# xyControl.net
KiCad netlist of a schematic drawn in EAGLE
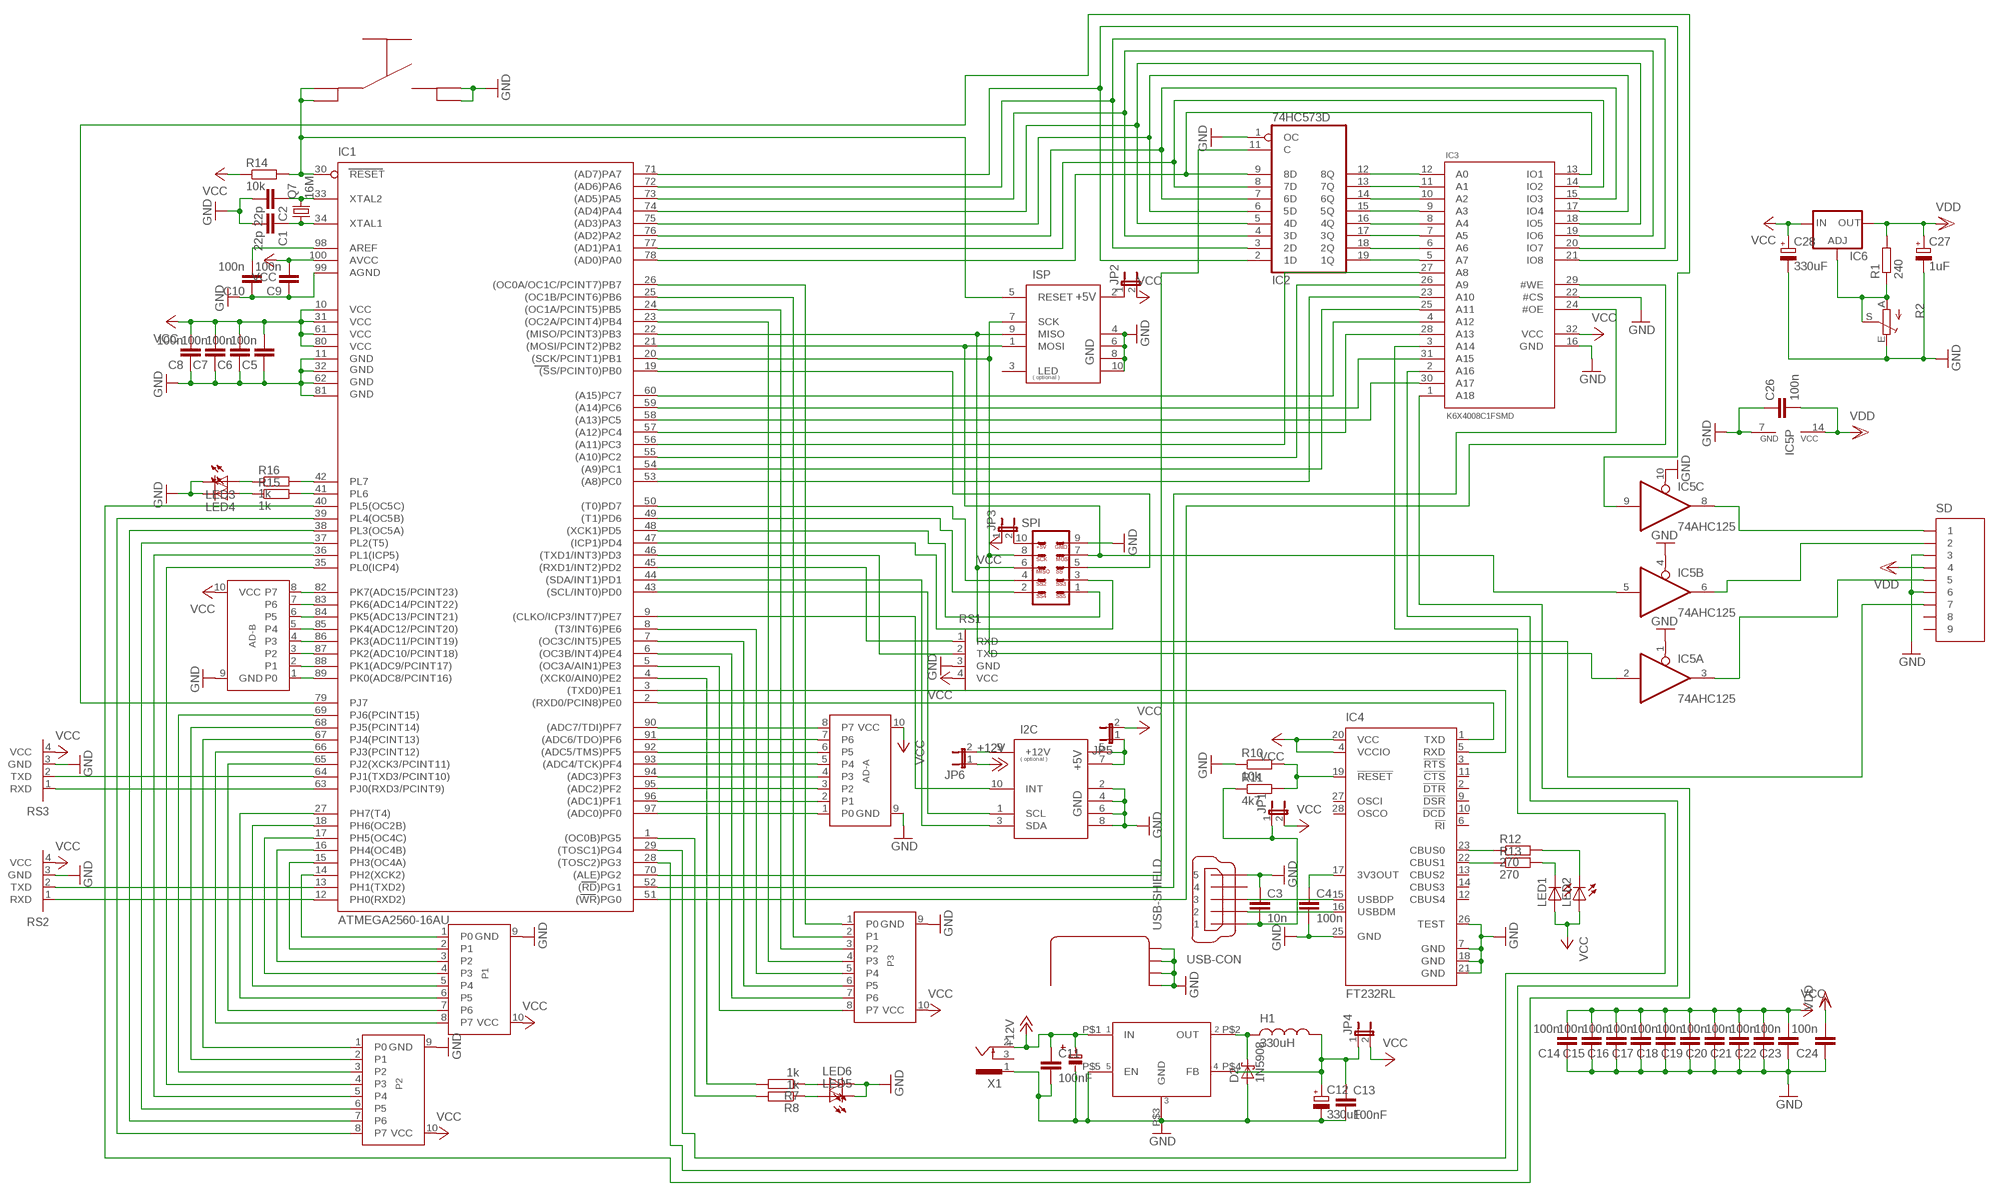
[diagram p0: schematic, sheet 1]

(export (version "E")
  (design (tool "Eeschema 10.0.6"))
  (components
    (comp (ref "AD-A")
      (value "PORT")
      (footprint "eagle-import:ML10")
      (libsource (lib "eagle-import") (part "PORT"))
    )
    (comp (ref "AD-B")
      (value "PORT")
      (footprint "eagle-import:ML10")
      (libsource (lib "eagle-import") (part "PORT"))
    )
    (comp (ref "C1")
      (value "22p")
      (footprint "eagle-import:C0603K")
      (libsource (lib "eagle-import") (part "C-EUC0603K"))
    )
    (comp (ref "C2")
      (value "22p")
      (footprint "eagle-import:C0603K")
      (libsource (lib "eagle-import") (part "C-EUC0603K"))
    )
    (comp (ref "C3")
      (value "10n")
      (footprint "eagle-import:C0603K")
      (libsource (lib "eagle-import") (part "C-EUC0603K"))
    )
    (comp (ref "C4")
      (value "100n")
      (footprint "eagle-import:C0603K")
      (libsource (lib "eagle-import") (part "C-EUC0603K"))
    )
    (comp (ref "C5")
      (value "100n")
      (footprint "eagle-import:C0603K")
      (libsource (lib "eagle-import") (part "C-EUC0603K"))
    )
    (comp (ref "C6")
      (value "100n")
      (footprint "eagle-import:C0603K")
      (libsource (lib "eagle-import") (part "C-EUC0603K"))
    )
    (comp (ref "C7")
      (value "100n")
      (footprint "eagle-import:C0603K")
      (libsource (lib "eagle-import") (part "C-EUC0603K"))
    )
    (comp (ref "C8")
      (value "100n")
      (footprint "eagle-import:C0603K")
      (libsource (lib "eagle-import") (part "C-EUC0603K"))
    )
    (comp (ref "C9")
      (value "100n")
      (footprint "eagle-import:C0603K")
      (libsource (lib "eagle-import") (part "C-EUC0603K"))
    )
    (comp (ref "C10")
      (value "100n")
      (footprint "eagle-import:C0603K")
      (libsource (lib "eagle-import") (part "C-EUC0603K"))
    )
    (comp (ref "C11")
      (value "100nF")
      (footprint "eagle-import:C0603K")
      (libsource (lib "eagle-import") (part "C-EUC0603K"))
    )
    (comp (ref "C12")
      (value "330uF")
      (footprint "eagle-import:PANASONIC_F")
      (libsource (lib "eagle-import") (part "CPOL-EUF"))
    )
    (comp (ref "C13")
      (value "100nF")
      (footprint "eagle-import:C0603K")
      (libsource (lib "eagle-import") (part "C-EUC0603K"))
    )
    (comp (ref "C14")
      (value "100n")
      (footprint "eagle-import:C0603K")
      (libsource (lib "eagle-import") (part "C-EUC0603K"))
    )
    (comp (ref "C15")
      (value "100n")
      (footprint "eagle-import:C0603K")
      (libsource (lib "eagle-import") (part "C-EUC0603K"))
    )
    (comp (ref "C16")
      (value "100n")
      (footprint "eagle-import:C0603K")
      (libsource (lib "eagle-import") (part "C-EUC0603K"))
    )
    (comp (ref "C17")
      (value "100n")
      (footprint "eagle-import:C0603K")
      (libsource (lib "eagle-import") (part "C-EUC0603K"))
    )
    (comp (ref "C18")
      (value "100n")
      (footprint "eagle-import:C0603K")
      (libsource (lib "eagle-import") (part "C-EUC0603K"))
    )
    (comp (ref "C19")
      (value "100n")
      (footprint "eagle-import:C0603K")
      (libsource (lib "eagle-import") (part "C-EUC0603K"))
    )
    (comp (ref "C20")
      (value "100n")
      (footprint "eagle-import:C0603K")
      (libsource (lib "eagle-import") (part "C-EUC0603K"))
    )
    (comp (ref "C21")
      (value "100n")
      (footprint "eagle-import:C0603K")
      (libsource (lib "eagle-import") (part "C-EUC0603K"))
    )
    (comp (ref "C22")
      (value "100n")
      (footprint "eagle-import:C0603K")
      (libsource (lib "eagle-import") (part "C-EUC0603K"))
    )
    (comp (ref "C23")
      (value "100n")
      (footprint "eagle-import:C0603K")
      (libsource (lib "eagle-import") (part "C-EUC0603K"))
    )
    (comp (ref "C24")
      (value "100n")
      (footprint "eagle-import:C0603K")
      (libsource (lib "eagle-import") (part "C-EUC0603K"))
    )
    (comp (ref "C25")
      (value "100uF")
      (footprint "eagle-import:ELKO_SMD_6.5")
      (libsource (lib "eagle-import") (part "ELKO"))
    )
    (comp (ref "C26")
      (value "100n")
      (footprint "eagle-import:C0603K")
      (libsource (lib "eagle-import") (part "C-EUC0603K"))
    )
    (comp (ref "C27")
      (value "1uF")
      (footprint "eagle-import:E2,5-6")
      (libsource (lib "eagle-import") (part "CPOL-EUE2.5-6"))
    )
    (comp (ref "C28")
      (value "330uF")
      (footprint "eagle-import:E5-10,5")
      (libsource (lib "eagle-import") (part "CPOL-EUE5-10.5"))
    )
    (comp (ref "D2")
      (value "1N5908")
      (footprint "eagle-import:C4111-15")
      (libsource (lib "eagle-import") (part "1N5908"))
    )
    (comp (ref "H1")
      (value "330uH")
      (footprint "eagle-import:PISR")
      (libsource (lib "eagle-import") (part "PISR_SPULE"))
    )
    (comp (ref "I2C")
      (value "I2C")
      (footprint "eagle-import:ML10")
      (libsource (lib "eagle-import") (part "I2C"))
    )
    (comp (ref "IC1")
      (value "ATMEGA2560-16AU")
      (footprint "eagle-import:TQFP100")
      (libsource (lib "eagle-import") (part "ATMEGAAU2560-16"))
    )
    (comp (ref "IC2")
      (value "74HC573D")
      (footprint "eagle-import:SO20W")
      (libsource (lib "eagle-import") (part "74573DHC"))
    )
    (comp (ref "IC3")
      (value "K6X4008C1FSMD")
      (footprint "eagle-import:SOP-32")
      (libsource (lib "eagle-import") (part "K6X4008C1FSMD"))
    )
    (comp (ref "IC4")
      (value "FT232RL")
      (footprint "eagle-import:SSOP28")
      (libsource (lib "eagle-import") (part "FT232RL"))
    )
    (comp (ref "IC5")
      (value "74AHC125")
      (footprint "eagle-import:SO14")
      (libsource (lib "eagle-import") (part "74125DHC"))
    )
    (comp (ref "IC6")
      (value "LM317L")
      (footprint "eagle-import:317L")
      (libsource (lib "eagle-import") (part "LM317L"))
    )
    (comp (ref "ISP")
      (value "AVR-ISP")
      (footprint "eagle-import:ML10")
      (libsource (lib "eagle-import") (part "AVR-ISP"))
    )
    (comp (ref "JP1")
      (value "JP1E")
      (footprint "eagle-import:JP1")
      (libsource (lib "eagle-import") (part "JP1E"))
    )
    (comp (ref "JP2")
      (value "JP1E")
      (footprint "eagle-import:JP1")
      (libsource (lib "eagle-import") (part "JP1E"))
    )
    (comp (ref "JP3")
      (value "JP1E")
      (footprint "eagle-import:JP1")
      (libsource (lib "eagle-import") (part "JP1E"))
    )
    (comp (ref "JP4")
      (value "JP1E")
      (footprint "eagle-import:JP1")
      (libsource (lib "eagle-import") (part "JP1E"))
    )
    (comp (ref "JP5")
      (value "JP1E")
      (footprint "eagle-import:JP1")
      (libsource (lib "eagle-import") (part "JP1E"))
    )
    (comp (ref "JP6")
      (value "JP1E")
      (footprint "eagle-import:JP1")
      (libsource (lib "eagle-import") (part "JP1E"))
    )
    (comp (ref "LED1")
      (value "LEDCHIP-LED0603")
      (footprint "eagle-import:CHIP-LED0603")
      (libsource (lib "eagle-import") (part "LEDCHIP-LED0603"))
    )
    (comp (ref "LED2")
      (value "LEDCHIP-LED0603")
      (footprint "eagle-import:CHIP-LED0603")
      (libsource (lib "eagle-import") (part "LEDCHIP-LED0603"))
    )
    (comp (ref "LED3")
      (value "LEDCHIP-LED0603")
      (footprint "eagle-import:CHIP-LED0603")
      (libsource (lib "eagle-import") (part "LEDCHIP-LED0603"))
    )
    (comp (ref "LED4")
      (value "LEDCHIP-LED0603")
      (footprint "eagle-import:CHIP-LED0603")
      (libsource (lib "eagle-import") (part "LEDCHIP-LED0603"))
    )
    (comp (ref "LED5")
      (value "LEDCHIP-LED0603")
      (footprint "eagle-import:CHIP-LED0603")
      (libsource (lib "eagle-import") (part "LEDCHIP-LED0603"))
    )
    (comp (ref "LED6")
      (value "LEDCHIP-LED0603")
      (footprint "eagle-import:CHIP-LED0603")
      (libsource (lib "eagle-import") (part "LEDCHIP-LED0603"))
    )
    (comp (ref "LM2576-5")
      (value "LM2576")
      (footprint "eagle-import:TO-220")
      (libsource (lib "eagle-import") (part "LM2576"))
    )
    (comp (ref "P1")
      (value "PORT")
      (footprint "eagle-import:ML10")
      (libsource (lib "eagle-import") (part "PORT"))
    )
    (comp (ref "P2")
      (value "PORT")
      (footprint "eagle-import:ML10")
      (libsource (lib "eagle-import") (part "PORT"))
    )
    (comp (ref "P3")
      (value "PORT")
      (footprint "eagle-import:ML10")
      (libsource (lib "eagle-import") (part "PORT"))
    )
    (comp (ref "Q7")
      (value "16M")
      (footprint "eagle-import:HC49_S")
      (libsource (lib "eagle-import") (part "CRYSTALHC49S"))
    )
    (comp (ref "R1")
      (value "240")
      (footprint "eagle-import:R0603")
      (libsource (lib "eagle-import") (part "R-EU_R0603"))
    )
    (comp (ref "R2")
      (value "POT_TRIM_EU-ST10")
      (footprint "eagle-import:POT_ST10")
      (libsource (lib "eagle-import") (part "POT_TRIM_EU-ST10"))
    )
    (comp (ref "R7")
      (value "1k")
      (footprint "eagle-import:R0603")
      (libsource (lib "eagle-import") (part "R-EU_R0603"))
    )
    (comp (ref "R8")
      (value "1k")
      (footprint "eagle-import:R0603")
      (libsource (lib "eagle-import") (part "R-EU_R0603"))
    )
    (comp (ref "R10")
      (value "10k")
      (footprint "eagle-import:R0603")
      (libsource (lib "eagle-import") (part "R-EU_R0603"))
    )
    (comp (ref "R11")
      (value "4k7")
      (footprint "eagle-import:R0603")
      (libsource (lib "eagle-import") (part "R-EU_R0603"))
    )
    (comp (ref "R12")
      (value "270")
      (footprint "eagle-import:R0603")
      (libsource (lib "eagle-import") (part "R-EU_R0603"))
    )
    (comp (ref "R13")
      (value "270")
      (footprint "eagle-import:R0603")
      (libsource (lib "eagle-import") (part "R-EU_R0603"))
    )
    (comp (ref "R14")
      (value "10k")
      (footprint "eagle-import:R0603")
      (libsource (lib "eagle-import") (part "R-EU_R0603"))
    )
    (comp (ref "R15")
      (value "1k")
      (footprint "eagle-import:R0603")
      (libsource (lib "eagle-import") (part "R-EU_R0603"))
    )
    (comp (ref "R16")
      (value "1k")
      (footprint "eagle-import:R0603")
      (libsource (lib "eagle-import") (part "R-EU_R0603"))
    )
    (comp (ref "RS1")
      (value "RS232_TTL")
      (footprint "eagle-import:1X04")
      (libsource (lib "eagle-import") (part "RS232_TTL"))
    )
    (comp (ref "RS2")
      (value "RS232_TTL")
      (footprint "eagle-import:1X04")
      (libsource (lib "eagle-import") (part "RS232_TTL"))
    )
    (comp (ref "RS3")
      (value "RS232_TTL")
      (footprint "eagle-import:1X04")
      (libsource (lib "eagle-import") (part "RS232_TTL"))
    )
    (comp (ref "SD")
      (value "FPS009-30003")
      (footprint "eagle-import:FPS009-3003")
      (fields (field (name "MPN") "FPS009-3003-BL"))
      (libsource (lib "eagle-import") (part "FPS009-30003"))
    )
    (comp (ref "SPI")
      (value "SPISTECKER")
      (footprint "eagle-import:ML10")
      (libsource (lib "eagle-import") (part "SPISTECKER"))
    )
    (comp (ref "T1")
      (value "0-XYTHOBUZ_TASTER")
      (footprint "eagle-import:0-XYTHOBUZ_SMDTASTER")
      (libsource (lib "eagle-import") (part "0-XYTHOBUZ_TASTER"))
    )
    (comp (ref "USB")
      (value "1_USER_USB-B-MINI-SMD")
      (footprint "eagle-import:1_USER_USB-B-MINI-SMD")
      (libsource (lib "eagle-import") (part "1_USER_USB-B-MINI-SMD"))
    )
    (comp (ref "X1")
      (value "CON-CONRAD_733980-62")
      (footprint "eagle-import:CON-CONRAD_733980-62")
      (libsource (lib "eagle-import") (part "CON-CONRAD_73398?0-62"))
    )
  )
  (nets
    (net (code "1") (name "+12V") (class "Default")
      (node (ref "C11") (pin "1") (pinfunction "1_1") (pintype "passive"))
      (node (ref "C25") (pin "P$2") (pinfunction "P$2_P$2") (pintype "bidirectional"))
      (node (ref "JP6") (pin "1") (pinfunction "1_1") (pintype "passive"))
      (node (ref "LM2576-5") (pin "P$1") (pinfunction "IN_P$1") (pintype "power_in"))
      (node (ref "X1") (pin "2") (pinfunction "2_2") (pintype "passive"))
    )
    (net (code "2") (name "GND") (class "Default")
      (node (ref "AD-A") (pin "9") (pinfunction "GND_9") (pintype "power_in"))
      (node (ref "AD-B") (pin "9") (pinfunction "GND_9") (pintype "power_in"))
      (node (ref "C1") (pin "2") (pinfunction "2_2") (pintype "passive"))
      (node (ref "C10") (pin "1") (pinfunction "1_1") (pintype "passive"))
      (node (ref "C11") (pin "2") (pinfunction "2_2") (pintype "passive"))
      (node (ref "C12") (pin "-") (pinfunction "-_-") (pintype "passive"))
      (node (ref "C13") (pin "2") (pinfunction "2_2") (pintype "passive"))
      (node (ref "C14") (pin "1") (pinfunction "1_1") (pintype "passive"))
      (node (ref "C15") (pin "1") (pinfunction "1_1") (pintype "passive"))
      (node (ref "C16") (pin "1") (pinfunction "1_1") (pintype "passive"))
      (node (ref "C17") (pin "1") (pinfunction "1_1") (pintype "passive"))
      (node (ref "C18") (pin "1") (pinfunction "1_1") (pintype "passive"))
      (node (ref "C19") (pin "1") (pinfunction "1_1") (pintype "passive"))
      (node (ref "C2") (pin "2") (pinfunction "2_2") (pintype "passive"))
      (node (ref "C20") (pin "1") (pinfunction "1_1") (pintype "passive"))
      (node (ref "C21") (pin "1") (pinfunction "1_1") (pintype "passive"))
      (node (ref "C22") (pin "1") (pinfunction "1_1") (pintype "passive"))
      (node (ref "C23") (pin "1") (pinfunction "1_1") (pintype "passive"))
      (node (ref "C24") (pin "1") (pinfunction "1_1") (pintype "passive"))
      (node (ref "C25") (pin "P$1") (pinfunction "P$1_P$1") (pintype "bidirectional"))
      (node (ref "C26") (pin "1") (pinfunction "1_1") (pintype "passive"))
      (node (ref "C27") (pin "-") (pinfunction "-_-") (pintype "passive"))
      (node (ref "C28") (pin "-") (pinfunction "-_-") (pintype "passive"))
      (node (ref "C3") (pin "1") (pinfunction "1_1") (pintype "passive"))
      (node (ref "C4") (pin "2") (pinfunction "2_2") (pintype "passive"))
      (node (ref "C5") (pin "1") (pinfunction "1_1") (pintype "passive"))
      (node (ref "C6") (pin "1") (pinfunction "1_1") (pintype "passive"))
      (node (ref "C7") (pin "1") (pinfunction "1_1") (pintype "passive"))
      (node (ref "C8") (pin "1") (pinfunction "1_1") (pintype "passive"))
      (node (ref "C9") (pin "1") (pinfunction "1_1") (pintype "passive"))
      (node (ref "D2") (pin "A") (pinfunction "A_A") (pintype "passive"))
      (node (ref "I2C") (pin "2") (pinfunction "GND_2") (pintype "power_in"))
      (node (ref "I2C") (pin "4") (pinfunction "GND_4") (pintype "power_in"))
      (node (ref "I2C") (pin "6") (pinfunction "GND_6") (pintype "power_in"))
      (node (ref "I2C") (pin "8") (pinfunction "GND_8") (pintype "power_in"))
      (node (ref "IC1") (pin "11") (pinfunction "GND_11") (pintype "power_in"))
      (node (ref "IC1") (pin "32") (pinfunction "GND1_32") (pintype "power_in"))
      (node (ref "IC1") (pin "62") (pinfunction "GND2_62") (pintype "power_in"))
      (node (ref "IC1") (pin "81") (pinfunction "GND3_81") (pintype "power_in"))
      (node (ref "IC1") (pin "99") (pinfunction "AGND_99") (pintype "power_in"))
      (node (ref "IC2") (pin "1") (pinfunction "OC_1") (pintype "input"))
      (node (ref "IC3") (pin "16") (pinfunction "GND_16") (pintype "power_in"))
      (node (ref "IC3") (pin "22") (pinfunction "#CS_22") (pintype "bidirectional"))
      (node (ref "IC4") (pin "18") (pinfunction "GND_18") (pintype "power_in"))
      (node (ref "IC4") (pin "21") (pinfunction "GND_21") (pintype "power_in"))
      (node (ref "IC4") (pin "25") (pinfunction "GND_25") (pintype "power_in"))
      (node (ref "IC4") (pin "26") (pinfunction "TEST_26") (pintype "input"))
      (node (ref "IC4") (pin "7") (pinfunction "GND_7") (pintype "power_in"))
      (node (ref "IC5") (pin "1") (pinfunction "OE_1") (pintype "input"))
      (node (ref "IC5") (pin "10") (pinfunction "OE_10") (pintype "input"))
      (node (ref "IC5") (pin "4") (pinfunction "OE_4") (pintype "input"))
      (node (ref "IC5") (pin "7") (pinfunction "GND_7") (pintype "power_in"))
      (node (ref "ISP") (pin "10") (pinfunction "GND_10") (pintype "power_in"))
      (node (ref "ISP") (pin "4") (pinfunction "GND_4") (pintype "power_in"))
      (node (ref "ISP") (pin "6") (pinfunction "GND_6") (pintype "power_in"))
      (node (ref "ISP") (pin "8") (pinfunction "GND_8") (pintype "power_in"))
      (node (ref "LED3") (pin "C") (pinfunction "C_C") (pintype "passive"))
      (node (ref "LED4") (pin "C") (pinfunction "C_C") (pintype "passive"))
      (node (ref "LED5") (pin "C") (pinfunction "C_C") (pintype "passive"))
      (node (ref "LED6") (pin "C") (pinfunction "C_C") (pintype "passive"))
      (node (ref "LM2576-5") (pin "P$3") (pinfunction "GND_P$3") (pintype "power_in"))
      (node (ref "LM2576-5") (pin "P$5") (pinfunction "EN_P$5") (pintype "input"))
      (node (ref "P1") (pin "9") (pinfunction "GND_9") (pintype "power_in"))
      (node (ref "P2") (pin "9") (pinfunction "GND_9") (pintype "power_in"))
      (node (ref "P3") (pin "9") (pinfunction "GND_9") (pintype "power_in"))
      (node (ref "R10") (pin "1") (pinfunction "1_1") (pintype "passive"))
      (node (ref "R2") (pin "E") (pinfunction "E_E") (pintype "passive"))
      (node (ref "RS1") (pin "3") (pinfunction "GND_3") (pintype "bidirectional"))
      (node (ref "RS2") (pin "3") (pinfunction "GND_3") (pintype "bidirectional"))
      (node (ref "RS3") (pin "3") (pinfunction "GND_3") (pintype "bidirectional"))
      (node (ref "SD") (pin "3") (pinfunction "3_3") (pintype "input"))
      (node (ref "SD") (pin "6") (pinfunction "6_6") (pintype "input"))
      (node (ref "SPI") (pin "9") (pinfunction "9_9") (pintype "passive"))
      (node (ref "T1") (pin "B") (pinfunction "B_B") (pintype "bidirectional"))
      (node (ref "T1") (pin "B2") (pinfunction "B2_B2") (pintype "bidirectional"))
      (node (ref "USB") (pin "5") (pinfunction "5_5") (pintype "input"))
      (node (ref "USB") (pin "M1") (pinfunction "S1_M1") (pintype "passive"))
      (node (ref "USB") (pin "M2") (pinfunction "S2_M2") (pintype "passive"))
      (node (ref "USB") (pin "M3") (pinfunction "S3_M3") (pintype "passive"))
      (node (ref "USB") (pin "M4") (pinfunction "S4_M4") (pintype "passive"))
      (node (ref "X1") (pin "1") (pinfunction "1_1") (pintype "passive"))
    )
    (net (code "3") (name "Net-(AD-A-P0)") (class "Default")
      (node (ref "AD-A") (pin "1") (pinfunction "P0_1") (pintype "bidirectional"))
      (node (ref "IC1") (pin "97") (pinfunction "(ADC0)PF0_97") (pintype "bidirectional"))
    )
    (net (code "4") (name "Net-(AD-A-P1)") (class "Default")
      (node (ref "AD-A") (pin "2") (pinfunction "P1_2") (pintype "bidirectional"))
      (node (ref "IC1") (pin "96") (pinfunction "(ADC1)PF1_96") (pintype "bidirectional"))
    )
    (net (code "5") (name "Net-(AD-A-P2)") (class "Default")
      (node (ref "AD-A") (pin "3") (pinfunction "P2_3") (pintype "bidirectional"))
      (node (ref "IC1") (pin "95") (pinfunction "(ADC2)PF2_95") (pintype "bidirectional"))
    )
    (net (code "6") (name "Net-(AD-A-P3)") (class "Default")
      (node (ref "AD-A") (pin "4") (pinfunction "P3_4") (pintype "bidirectional"))
      (node (ref "IC1") (pin "94") (pinfunction "(ADC3)PF3_94") (pintype "bidirectional"))
    )
    (net (code "7") (name "Net-(AD-A-P4)") (class "Default")
      (node (ref "AD-A") (pin "5") (pinfunction "P4_5") (pintype "bidirectional"))
      (node (ref "IC1") (pin "93") (pinfunction "(ADC4/TCK)PF4_93") (pintype "bidirectional"))
    )
    (net (code "8") (name "Net-(AD-A-P5)") (class "Default")
      (node (ref "AD-A") (pin "6") (pinfunction "P5_6") (pintype "bidirectional"))
      (node (ref "IC1") (pin "92") (pinfunction "(ADC5/TMS)PF5_92") (pintype "bidirectional"))
    )
    (net (code "9") (name "Net-(AD-A-P6)") (class "Default")
      (node (ref "AD-A") (pin "7") (pinfunction "P6_7") (pintype "bidirectional"))
      (node (ref "IC1") (pin "91") (pinfunction "(ADC6/TDO)PF6_91") (pintype "bidirectional"))
    )
    (net (code "10") (name "Net-(AD-A-P7)") (class "Default")
      (node (ref "AD-A") (pin "8") (pinfunction "P7_8") (pintype "bidirectional"))
      (node (ref "IC1") (pin "90") (pinfunction "(ADC7/TDI)PF7_90") (pintype "bidirectional"))
    )
    (net (code "11") (name "Net-(AD-B-P0)") (class "Default")
      (node (ref "AD-B") (pin "1") (pinfunction "P0_1") (pintype "bidirectional"))
      (node (ref "IC1") (pin "89") (pinfunction "PK0(ADC8/PCINT16)_89") (pintype "bidirectional"))
    )
    (net (code "12") (name "Net-(AD-B-P1)") (class "Default")
      (node (ref "AD-B") (pin "2") (pinfunction "P1_2") (pintype "bidirectional"))
      (node (ref "IC1") (pin "88") (pinfunction "PK1(ADC9/PCINT17)_88") (pintype "bidirectional"))
    )
    (net (code "13") (name "Net-(AD-B-P2)") (class "Default")
      (node (ref "AD-B") (pin "3") (pinfunction "P2_3") (pintype "bidirectional"))
      (node (ref "IC1") (pin "87") (pinfunction "PK2(ADC10/PCINT18)_87") (pintype "bidirectional"))
    )
    (net (code "14") (name "Net-(AD-B-P3)") (class "Default")
      (node (ref "AD-B") (pin "4") (pinfunction "P3_4") (pintype "bidirectional"))
      (node (ref "IC1") (pin "86") (pinfunction "PK3(ADC11/PCINT19)_86") (pintype "bidirectional"))
    )
    (net (code "15") (name "Net-(AD-B-P4)") (class "Default")
      (node (ref "AD-B") (pin "5") (pinfunction "P4_5") (pintype "bidirectional"))
      (node (ref "IC1") (pin "85") (pinfunction "PK4(ADC12/PCINT20)_85") (pintype "bidirectional"))
    )
    (net (code "16") (name "Net-(AD-B-P5)") (class "Default")
      (node (ref "AD-B") (pin "6") (pinfunction "P5_6") (pintype "bidirectional"))
      (node (ref "IC1") (pin "84") (pinfunction "PK5(ADC13/PCINT21)_84") (pintype "bidirectional"))
    )
    (net (code "17") (name "Net-(AD-B-P6)") (class "Default")
      (node (ref "AD-B") (pin "7") (pinfunction "P6_7") (pintype "bidirectional"))
      (node (ref "IC1") (pin "83") (pinfunction "PK6(ADC14/PCINT22)_83") (pintype "bidirectional"))
    )
    (net (code "18") (name "Net-(AD-B-P7)") (class "Default")
      (node (ref "AD-B") (pin "8") (pinfunction "P7_8") (pintype "bidirectional"))
      (node (ref "IC1") (pin "82") (pinfunction "PK7(ADC15/PCINT23)_82") (pintype "bidirectional"))
    )
    (net (code "19") (name "Net-(C3-Pad2)") (class "Default")
      (node (ref "C3") (pin "2") (pinfunction "2_2") (pintype "passive"))
      (node (ref "JP1") (pin "1") (pinfunction "1_1") (pintype "passive"))
      (node (ref "R11") (pin "1") (pinfunction "1_1") (pintype "passive"))
      (node (ref "USB") (pin "1") (pinfunction "1_1") (pintype "input"))
    )
    (net (code "20") (name "Net-(I2C-+5V-Pad5)") (class "Default")
      (node (ref "I2C") (pin "5") (pinfunction "+5V_5") (pintype "power_in"))
      (node (ref "I2C") (pin "7") (pinfunction "+5V_7") (pintype "power_in"))
      (node (ref "JP5") (pin "1") (pinfunction "1_1") (pintype "passive"))
    )
    (net (code "21") (name "Net-(I2C-+12V)") (class "Default")
      (node (ref "I2C") (pin "9") (pinfunction "+12V_9") (pintype "bidirectional"))
      (node (ref "JP6") (pin "2") (pinfunction "2_2") (pintype "passive"))
    )
    (net (code "22") (name "Net-(I2C-INT)") (class "Default")
      (node (ref "I2C") (pin "10") (pinfunction "INT_10") (pintype "output"))
      (node (ref "IC1") (pin "9") (pinfunction "(CLKO/ICP3/INT7)PE7_9") (pintype "bidirectional"))
    )
    (net (code "23") (name "Net-(I2C-SCL)") (class "Default")
      (node (ref "I2C") (pin "1") (pinfunction "SCL_1") (pintype "input"))
      (node (ref "IC1") (pin "43") (pinfunction "(SCL/INT0)PD0_43") (pintype "bidirectional"))
    )
    (net (code "24") (name "Net-(I2C-SDA)") (class "Default")
      (node (ref "I2C") (pin "3") (pinfunction "SDA_3") (pintype "bidirectional"))
      (node (ref "IC1") (pin "44") (pinfunction "(SDA/INT1)PD1_44") (pintype "bidirectional"))
    )
    (net (code "25") (name "Net-(IC1-(A8)PC0)") (class "Default")
      (node (ref "IC1") (pin "53") (pinfunction "(A8)PC0_53") (pintype "bidirectional"))
      (node (ref "IC3") (pin "23") (pinfunction "A10_23") (pintype "bidirectional"))
    )
    (net (code "26") (name "Net-(IC1-(A9)PC1)") (class "Default")
      (node (ref "IC1") (pin "54") (pinfunction "(A9)PC1_54") (pintype "bidirectional"))
      (node (ref "IC3") (pin "25") (pinfunction "A11_25") (pintype "bidirectional"))
    )
    (net (code "27") (name "Net-(IC1-(A10)PC2)") (class "Default")
      (node (ref "IC1") (pin "55") (pinfunction "(A10)PC2_55") (pintype "bidirectional"))
      (node (ref "IC3") (pin "26") (pinfunction "A9_26") (pintype "bidirectional"))
    )
    (net (code "28") (name "Net-(IC1-(A11)PC3)") (class "Default")
      (node (ref "IC1") (pin "56") (pinfunction "(A11)PC3_56") (pintype "bidirectional"))
      (node (ref "IC3") (pin "27") (pinfunction "A8_27") (pintype "bidirectional"))
    )
    (net (code "29") (name "Net-(IC1-(A12)PC4)") (class "Default")
      (node (ref "IC1") (pin "57") (pinfunction "(A12)PC4_57") (pintype "bidirectional"))
      (node (ref "IC3") (pin "28") (pinfunction "A13_28") (pintype "bidirectional"))
    )
    (net (code "30") (name "Net-(IC1-(A13)PC5)") (class "Default")
      (node (ref "IC1") (pin "58") (pinfunction "(A13)PC5_58") (pintype "bidirectional"))
      (node (ref "IC3") (pin "30") (pinfunction "A17_30") (pintype "bidirectional"))
    )
    (net (code "31") (name "Net-(IC1-(A14)PC6)") (class "Default")
      (node (ref "IC1") (pin "59") (pinfunction "(A14)PC6_59") (pintype "bidirectional"))
      (node (ref "IC3") (pin "31") (pinfunction "A15_31") (pintype "bidirectional"))
    )
    (net (code "32") (name "Net-(IC1-(A15)PC7)") (class "Default")
      (node (ref "IC1") (pin "60") (pinfunction "(A15)PC7_60") (pintype "bidirectional"))
      (node (ref "IC3") (pin "4") (pinfunction "A12_4") (pintype "bidirectional"))
    )
    (net (code "33") (name "Net-(IC1-(AD0)PA0)") (class "Default")
      (node (ref "IC1") (pin "78") (pinfunction "(AD0)PA0_78") (pintype "bidirectional"))
      (node (ref "IC2") (pin "9") (pinfunction "8D_9") (pintype "input"))
      (node (ref "IC3") (pin "13") (pinfunction "IO1_13") (pintype "bidirectional"))
    )
    (net (code "34") (name "Net-(IC1-(AD1)PA1)") (class "Default")
      (node (ref "IC1") (pin "77") (pinfunction "(AD1)PA1_77") (pintype "bidirectional"))
      (node (ref "IC2") (pin "8") (pinfunction "7D_8") (pintype "input"))
      (node (ref "IC3") (pin "14") (pinfunction "IO2_14") (pintype "bidirectional"))
    )
    (net (code "35") (name "Net-(IC1-(AD2)PA2)") (class "Default")
      (node (ref "IC1") (pin "76") (pinfunction "(AD2)PA2_76") (pintype "bidirectional"))
      (node (ref "IC2") (pin "7") (pinfunction "6D_7") (pintype "input"))
      (node (ref "IC3") (pin "15") (pinfunction "IO3_15") (pintype "bidirectional"))
    )
    (net (code "36") (name "Net-(IC1-(AD3)PA3)") (class "Default")
      (node (ref "IC1") (pin "75") (pinfunction "(AD3)PA3_75") (pintype "bidirectional"))
      (node (ref "IC2") (pin "6") (pinfunction "5D_6") (pintype "input"))
      (node (ref "IC3") (pin "17") (pinfunction "IO4_17") (pintype "bidirectional"))
    )
    (net (code "37") (name "Net-(IC1-(AD4)PA4)") (class "Default")
      (node (ref "IC1") (pin "74") (pinfunction "(AD4)PA4_74") (pintype "bidirectional"))
      (node (ref "IC2") (pin "5") (pinfunction "4D_5") (pintype "input"))
      (node (ref "IC3") (pin "18") (pinfunction "IO5_18") (pintype "bidirectional"))
    )
    (net (code "38") (name "Net-(IC1-(AD5)PA5)") (class "Default")
      (node (ref "IC1") (pin "73") (pinfunction "(AD5)PA5_73") (pintype "bidirectional"))
      (node (ref "IC2") (pin "4") (pinfunction "3D_4") (pintype "input"))
      (node (ref "IC3") (pin "19") (pinfunction "IO6_19") (pintype "bidirectional"))
    )
    (net (code "39") (name "Net-(IC1-(AD6)PA6)") (class "Default")
      (node (ref "IC1") (pin "72") (pinfunction "(AD6)PA6_72") (pintype "bidirectional"))
      (node (ref "IC2") (pin "3") (pinfunction "2D_3") (pintype "input"))
      (node (ref "IC3") (pin "20") (pinfunction "IO7_20") (pintype "bidirectional"))
    )
    (net (code "40") (name "Net-(IC1-(AD7)PA7)") (class "Default")
      (node (ref "IC1") (pin "71") (pinfunction "(AD7)PA7_71") (pintype "bidirectional"))
      (node (ref "IC2") (pin "2") (pinfunction "1D_2") (pintype "input"))
      (node (ref "IC3") (pin "21") (pinfunction "IO8_21") (pintype "bidirectional"))
    )
    (net (code "41") (name "Net-(IC1-(ALE)PG2)") (class "Default")
      (node (ref "IC1") (pin "70") (pinfunction "(ALE)PG2_70") (pintype "bidirectional"))
      (node (ref "IC2") (pin "11") (pinfunction "C_11") (pintype "input"))
    )
    (net (code "42") (name "Net-(IC1-(ICP1)PD4)") (class "Default")
      (node (ref "IC1") (pin "47") (pinfunction "(ICP1)PD4_47") (pintype "bidirectional"))
      (node (ref "SPI") (pin "3") (pinfunction "3_3") (pintype "passive"))
    )
    (net (code "43") (name "Net-(IC1-(MISO{slash}PCINT3)PB3)") (class "Default")
      (node (ref "IC1") (pin "22") (pinfunction "(MISO/PCINT3)PB3_22") (pintype "bidirectional"))
      (node (ref "ISP") (pin "9") (pinfunction "MISO_9") (pintype "bidirectional"))
      (node (ref "SD") (pin "7") (pinfunction "7_7") (pintype "input"))
      (node (ref "SPI") (pin "6") (pinfunction "6_6") (pintype "passive"))
    )
    (net (code "44") (name "Net-(IC1-(MOSI{slash}PCINT2)PB2)") (class "Default")
      (node (ref "IC1") (pin "21") (pinfunction "(MOSI/PCINT2)PB2_21") (pintype "bidirectional"))
      (node (ref "IC5") (pin "5") (pinfunction "I_5") (pintype "input"))
      (node (ref "ISP") (pin "1") (pinfunction "MOSI_1") (pintype "bidirectional"))
      (node (ref "SPI") (pin "7") (pinfunction "7_7") (pintype "passive"))
    )
    (net (code "45") (name "Net-(IC1-(OC0A{slash}OC1C{slash}PCINT7)PB7)") (class "Default")
      (node (ref "IC1") (pin "26") (pinfunction "(OC0A/OC1C/PCINT7)PB7_26") (pintype "bidirectional"))
      (node (ref "P3") (pin "1") (pinfunction "P0_1") (pintype "bidirectional"))
    )
    (net (code "46") (name "Net-(IC1-(OC0B)PG5)") (class "Default")
      (node (ref "IC1") (pin "1") (pinfunction "(OC0B)PG5_1") (pintype "bidirectional"))
      (node (ref "R8") (pin "2") (pinfunction "2_2") (pintype "passive"))
    )
    (net (code "47") (name "Net-(IC1-(OC1A{slash}PCINT5)PB5)") (class "Default")
      (node (ref "IC1") (pin "24") (pinfunction "(OC1A/PCINT5)PB5_24") (pintype "bidirectional"))
      (node (ref "P3") (pin "3") (pinfunction "P2_3") (pintype "bidirectional"))
    )
    (net (code "48") (name "Net-(IC1-(OC1B{slash}PCINT6)PB6)") (class "Default")
      (node (ref "IC1") (pin "25") (pinfunction "(OC1B/PCINT6)PB6_25") (pintype "bidirectional"))
      (node (ref "P3") (pin "2") (pinfunction "P1_2") (pintype "bidirectional"))
    )
    (net (code "49") (name "Net-(IC1-(OC2A{slash}PCINT4)PB4)") (class "Default")
      (node (ref "IC1") (pin "23") (pinfunction "(OC2A/PCINT4)PB4_23") (pintype "bidirectional"))
      (node (ref "P3") (pin "4") (pinfunction "P3_4") (pintype "bidirectional"))
    )
    (net (code "50") (name "Net-(IC1-(OC3A{slash}AIN1)PE3)") (class "Default")
      (node (ref "IC1") (pin "5") (pinfunction "(OC3A/AIN1)PE3_5") (pintype "bidirectional"))
      (node (ref "P3") (pin "8") (pinfunction "P7_8") (pintype "bidirectional"))
    )
    (net (code "51") (name "Net-(IC1-(OC3B{slash}INT4)PE4)") (class "Default")
      (node (ref "IC1") (pin "6") (pinfunction "(OC3B/INT4)PE4_6") (pintype "bidirectional"))
      (node (ref "P3") (pin "7") (pinfunction "P6_7") (pintype "bidirectional"))
    )
    (net (code "52") (name "Net-(IC1-(OC3C{slash}INT5)PE5)") (class "Default")
      (node (ref "IC1") (pin "7") (pinfunction "(OC3C/INT5)PE5_7") (pintype "bidirectional"))
      (node (ref "P3") (pin "6") (pinfunction "P5_6") (pintype "bidirectional"))
    )
    (net (code "53") (name "Net-(IC1-(RD)PG1)") (class "Default")
      (node (ref "IC1") (pin "52") (pinfunction "(RD)PG1_52") (pintype "bidirectional"))
      (node (ref "IC3") (pin "24") (pinfunction "#OE_24") (pintype "bidirectional"))
    )
    (net (code "54") (name "Net-(IC1-(RXD0{slash}PCIN8)PE0)") (class "Default")
      (node (ref "IC1") (pin "2") (pinfunction "(RXD0/PCIN8)PE0_2") (pintype "bidirectional"))
      (node (ref "IC4") (pin "1") (pinfunction "TXD_1") (pintype "output"))
    )
    (net (code "55") (name "Net-(IC1-(RXD1{slash}INT2)PD2)") (class "Default")
      (node (ref "IC1") (pin "45") (pinfunction "(RXD1/INT2)PD2_45") (pintype "bidirectional"))
      (node (ref "RS1") (pin "1") (pinfunction "RXD_1") (pintype "bidirectional"))
    )
    (net (code "56") (name "Net-(IC1-(SCK{slash}PCINT1)PB1)") (class "Default")
      (node (ref "IC1") (pin "20") (pinfunction "(SCK/PCINT1)PB1_20") (pintype "bidirectional"))
      (node (ref "IC5") (pin "2") (pinfunction "I_2") (pintype "input"))
      (node (ref "ISP") (pin "7") (pinfunction "SCK_7") (pintype "input"))
      (node (ref "SPI") (pin "8") (pinfunction "8_8") (pintype "passive"))
    )
    (net (code "57") (name "Net-(IC1-(SS{slash}PCINT0)PB0)") (class "Default")
      (node (ref "IC1") (pin "19") (pinfunction "(SS/PCINT0)PB0_19") (pintype "bidirectional"))
      (node (ref "SPI") (pin "5") (pinfunction "5_5") (pintype "passive"))
    )
    (net (code "58") (name "Net-(IC1-(T0)PD7)") (class "Default")
      (node (ref "IC1") (pin "50") (pinfunction "(T0)PD7_50") (pintype "bidirectional"))
      (node (ref "SPI") (pin "4") (pinfunction "4_4") (pintype "passive"))
    )
    (net (code "59") (name "Net-(IC1-(T1)PD6)") (class "Default")
      (node (ref "IC1") (pin "49") (pinfunction "(T1)PD6_49") (pintype "bidirectional"))
      (node (ref "SPI") (pin "2") (pinfunction "2_2") (pintype "passive"))
    )
    (net (code "60") (name "Net-(IC1-(T3{slash}INT6)PE6)") (class "Default")
      (node (ref "IC1") (pin "8") (pinfunction "(T3/INT6)PE6_8") (pintype "bidirectional"))
      (node (ref "P3") (pin "5") (pinfunction "P4_5") (pintype "bidirectional"))
    )
    (net (code "61") (name "Net-(IC1-(TOSC1)PG4)") (class "Default")
      (node (ref "IC1") (pin "29") (pinfunction "(TOSC1)PG4_29") (pintype "bidirectional"))
      (node (ref "IC3") (pin "3") (pinfunction "A14_3") (pintype "bidirectional"))
    )
    (net (code "62") (name "Net-(IC1-(TOSC2)PG3)") (class "Default")
      (node (ref "IC1") (pin "28") (pinfunction "(TOSC2)PG3_28") (pintype "bidirectional"))
      (node (ref "IC3") (pin "2") (pinfunction "A16_2") (pintype "bidirectional"))
    )
    (net (code "63") (name "Net-(IC1-(TXD0)PE1)") (class "Default")
      (node (ref "IC1") (pin "3") (pinfunction "(TXD0)PE1_3") (pintype "bidirectional"))
      (node (ref "IC4") (pin "5") (pinfunction "RXD_5") (pintype "input"))
    )
    (net (code "64") (name "Net-(IC1-(TXD1{slash}INT3)PD3)") (class "Default")
      (node (ref "IC1") (pin "46") (pinfunction "(TXD1/INT3)PD3_46") (pintype "bidirectional"))
      (node (ref "RS1") (pin "2") (pinfunction "TXD_2") (pintype "bidirectional"))
    )
    (net (code "65") (name "Net-(IC1-(WR)PG0)") (class "Default")
      (node (ref "IC1") (pin "51") (pinfunction "(WR)PG0_51") (pintype "bidirectional"))
      (node (ref "IC3") (pin "29") (pinfunction "#WE_29") (pintype "bidirectional"))
    )
    (net (code "66") (name "Net-(IC1-(XCK0{slash}AIN0)PE2)") (class "Default")
      (node (ref "IC1") (pin "4") (pinfunction "(XCK0/AIN0)PE2_4") (pintype "bidirectional"))
      (node (ref "R7") (pin "2") (pinfunction "2_2") (pintype "passive"))
    )
    (net (code "67") (name "Net-(IC1-(XCK1)PD5)") (class "Default")
      (node (ref "IC1") (pin "48") (pinfunction "(XCK1)PD5_48") (pintype "bidirectional"))
      (node (ref "SPI") (pin "1") (pinfunction "1_1") (pintype "passive"))
    )
    (net (code "68") (name "Net-(IC1-AREF)") (class "Default")
      (node (ref "C10") (pin "2") (pinfunction "2_2") (pintype "passive"))
      (node (ref "IC1") (pin "98") (pinfunction "AREF_98") (pintype "bidirectional"))
    )
    (net (code "69") (name "Net-(IC1-PH0(RXD2))") (class "Default")
      (node (ref "IC1") (pin "12") (pinfunction "PH0(RXD2)_12") (pintype "bidirectional"))
      (node (ref "RS2") (pin "1") (pinfunction "RXD_1") (pintype "bidirectional"))
    )
    (net (code "70") (name "Net-(IC1-PH1(TXD2))") (class "Default")
      (node (ref "IC1") (pin "13") (pinfunction "PH1(TXD2)_13") (pintype "bidirectional"))
      (node (ref "RS2") (pin "2") (pinfunction "TXD_2") (pintype "bidirectional"))
    )
    (net (code "71") (name "Net-(IC1-PH2(XCK2))") (class "Default")
      (node (ref "IC1") (pin "14") (pinfunction "PH2(XCK2)_14") (pintype "bidirectional"))
      (node (ref "P1") (pin "1") (pinfunction "P0_1") (pintype "bidirectional"))
    )
    (net (code "72") (name "Net-(IC1-PH3(OC4A))") (class "Default")
      (node (ref "IC1") (pin "15") (pinfunction "PH3(OC4A)_15") (pintype "bidirectional"))
      (node (ref "P1") (pin "2") (pinfunction "P1_2") (pintype "bidirectional"))
    )
    (net (code "73") (name "Net-(IC1-PH4(OC4B))") (class "Default")
      (node (ref "IC1") (pin "16") (pinfunction "PH4(OC4B)_16") (pintype "bidirectional"))
      (node (ref "P1") (pin "3") (pinfunction "P2_3") (pintype "bidirectional"))
    )
    (net (code "74") (name "Net-(IC1-PH5(OC4C))") (class "Default")
      (node (ref "IC1") (pin "17") (pinfunction "PH5(OC4C)_17") (pintype "bidirectional"))
      (node (ref "P1") (pin "4") (pinfunction "P3_4") (pintype "bidirectional"))
    )
    (net (code "75") (name "Net-(IC1-PH6(OC2B))") (class "Default")
      (node (ref "IC1") (pin "18") (pinfunction "PH6(OC2B)_18") (pintype "bidirectional"))
      (node (ref "P1") (pin "5") (pinfunction "P4_5") (pintype "bidirectional"))
    )
    (net (code "76") (name "Net-(IC1-PH7(T4))") (class "Default")
      (node (ref "IC1") (pin "27") (pinfunction "PH7(T4)_27") (pintype "bidirectional"))
      (node (ref "P1") (pin "6") (pinfunction "P5_6") (pintype "bidirectional"))
    )
    (net (code "77") (name "Net-(IC1-PJ0(RXD3{slash}PCINT9))") (class "Default")
      (node (ref "IC1") (pin "63") (pinfunction "PJ0(RXD3/PCINT9)_63") (pintype "bidirectional"))
      (node (ref "RS3") (pin "1") (pinfunction "RXD_1") (pintype "bidirectional"))
    )
    (net (code "78") (name "Net-(IC1-PJ1(TXD3{slash}PCINT10))") (class "Default")
      (node (ref "IC1") (pin "64") (pinfunction "PJ1(TXD3/PCINT10)_64") (pintype "bidirectional"))
      (node (ref "RS3") (pin "2") (pinfunction "TXD_2") (pintype "bidirectional"))
    )
    (net (code "79") (name "Net-(IC1-PJ2(XCK3{slash}PCINT11))") (class "Default")
      (node (ref "IC1") (pin "65") (pinfunction "PJ2(XCK3/PCINT11)_65") (pintype "bidirectional"))
      (node (ref "P1") (pin "7") (pinfunction "P6_7") (pintype "bidirectional"))
    )
    (net (code "80") (name "Net-(IC1-PJ3(PCINT12))") (class "Default")
      (node (ref "IC1") (pin "66") (pinfunction "PJ3(PCINT12)_66") (pintype "bidirectional"))
      (node (ref "P1") (pin "8") (pinfunction "P7_8") (pintype "bidirectional"))
    )
    (net (code "81") (name "Net-(IC1-PJ4(PCINT13))") (class "Default")
      (node (ref "IC1") (pin "67") (pinfunction "PJ4(PCINT13)_67") (pintype "bidirectional"))
      (node (ref "P2") (pin "1") (pinfunction "P0_1") (pintype "bidirectional"))
    )
    (net (code "82") (name "Net-(IC1-PJ5(PCINT14))") (class "Default")
      (node (ref "IC1") (pin "68") (pinfunction "PJ5(PCINT14)_68") (pintype "bidirectional"))
      (node (ref "P2") (pin "2") (pinfunction "P1_2") (pintype "bidirectional"))
    )
    (net (code "83") (name "Net-(IC1-PJ6(PCINT15))") (class "Default")
      (node (ref "IC1") (pin "69") (pinfunction "PJ6(PCINT15)_69") (pintype "bidirectional"))
      (node (ref "P2") (pin "3") (pinfunction "P2_3") (pintype "bidirectional"))
    )
    (net (code "84") (name "Net-(IC1-PJ7)") (class "Default")
      (node (ref "IC1") (pin "79") (pinfunction "PJ7_79") (pintype "bidirectional"))
      (node (ref "IC5") (pin "9") (pinfunction "I_9") (pintype "input"))
    )
    (net (code "85") (name "Net-(IC1-PL0(ICP4))") (class "Default")
      (node (ref "IC1") (pin "35") (pinfunction "PL0(ICP4)_35") (pintype "bidirectional"))
      (node (ref "P2") (pin "4") (pinfunction "P3_4") (pintype "bidirectional"))
    )
    (net (code "86") (name "Net-(IC1-PL1(ICP5))") (class "Default")
      (node (ref "IC1") (pin "36") (pinfunction "PL1(ICP5)_36") (pintype "bidirectional"))
      (node (ref "P2") (pin "5") (pinfunction "P4_5") (pintype "bidirectional"))
    )
    (net (code "87") (name "Net-(IC1-PL2(T5))") (class "Default")
      (node (ref "IC1") (pin "37") (pinfunction "PL2(T5)_37") (pintype "bidirectional"))
      (node (ref "P2") (pin "6") (pinfunction "P5_6") (pintype "bidirectional"))
    )
    (net (code "88") (name "Net-(IC1-PL3(OC5A))") (class "Default")
      (node (ref "IC1") (pin "38") (pinfunction "PL3(OC5A)_38") (pintype "bidirectional"))
      (node (ref "P2") (pin "7") (pinfunction "P6_7") (pintype "bidirectional"))
    )
    (net (code "89") (name "Net-(IC1-PL4(OC5B))") (class "Default")
      (node (ref "IC1") (pin "39") (pinfunction "PL4(OC5B)_39") (pintype "bidirectional"))
      (node (ref "P2") (pin "8") (pinfunction "P7_8") (pintype "bidirectional"))
    )
    (net (code "90") (name "Net-(IC1-PL5(OC5C))") (class "Default")
      (node (ref "IC1") (pin "40") (pinfunction "PL5(OC5C)_40") (pintype "bidirectional"))
      (node (ref "IC3") (pin "1") (pinfunction "A18_1") (pintype "bidirectional"))
    )
    (net (code "91") (name "Net-(IC1-PL6)") (class "Default")
      (node (ref "IC1") (pin "41") (pinfunction "PL6_41") (pintype "bidirectional"))
      (node (ref "R15") (pin "2") (pinfunction "2_2") (pintype "passive"))
    )
    (net (code "92") (name "Net-(IC1-PL7)") (class "Default")
      (node (ref "IC1") (pin "42") (pinfunction "PL7_42") (pintype "bidirectional"))
      (node (ref "R16") (pin "2") (pinfunction "2_2") (pintype "passive"))
    )
    (net (code "93") (name "Net-(IC1-RESET)") (class "Default")
      (node (ref "IC1") (pin "30") (pinfunction "RESET_30") (pintype "input"))
      (node (ref "ISP") (pin "5") (pinfunction "RESET_5") (pintype "input"))
      (node (ref "R14") (pin "2") (pinfunction "2_2") (pintype "passive"))
      (node (ref "T1") (pin "A") (pinfunction "A_A") (pintype "bidirectional"))
      (node (ref "T1") (pin "A2") (pinfunction "A2_A2") (pintype "bidirectional"))
    )
    (net (code "94") (name "Net-(IC1-XTAL1)") (class "Default")
      (node (ref "C1") (pin "1") (pinfunction "1_1") (pintype "passive"))
      (node (ref "IC1") (pin "34") (pinfunction "XTAL1_34") (pintype "input"))
      (node (ref "Q7") (pin "1") (pinfunction "1_1") (pintype "passive"))
    )
    (net (code "95") (name "Net-(IC1-XTAL2)") (class "Default")
      (node (ref "C2") (pin "1") (pinfunction "1_1") (pintype "passive"))
      (node (ref "IC1") (pin "33") (pinfunction "XTAL2_33") (pintype "output"))
      (node (ref "Q7") (pin "2") (pinfunction "2_2") (pintype "passive"))
    )
    (net (code "96") (name "Net-(IC2A-1Q)") (class "Default")
      (node (ref "IC2") (pin "19") (pinfunction "1Q_19") (pintype "tri_state"))
      (node (ref "IC3") (pin "5") (pinfunction "A7_5") (pintype "bidirectional"))
    )
    (net (code "97") (name "Net-(IC2A-2Q)") (class "Default")
      (node (ref "IC2") (pin "18") (pinfunction "2Q_18") (pintype "tri_state"))
      (node (ref "IC3") (pin "6") (pinfunction "A6_6") (pintype "bidirectional"))
    )
    (net (code "98") (name "Net-(IC2A-3Q)") (class "Default")
      (node (ref "IC2") (pin "17") (pinfunction "3Q_17") (pintype "tri_state"))
      (node (ref "IC3") (pin "7") (pinfunction "A5_7") (pintype "bidirectional"))
    )
    (net (code "99") (name "Net-(IC2A-4Q)") (class "Default")
      (node (ref "IC2") (pin "16") (pinfunction "4Q_16") (pintype "tri_state"))
      (node (ref "IC3") (pin "8") (pinfunction "A4_8") (pintype "bidirectional"))
    )
    (net (code "100") (name "Net-(IC2A-5Q)") (class "Default")
      (node (ref "IC2") (pin "15") (pinfunction "5Q_15") (pintype "tri_state"))
      (node (ref "IC3") (pin "9") (pinfunction "A3_9") (pintype "bidirectional"))
    )
    (net (code "101") (name "Net-(IC2A-6Q)") (class "Default")
      (node (ref "IC2") (pin "14") (pinfunction "6Q_14") (pintype "tri_state"))
      (node (ref "IC3") (pin "10") (pinfunction "A2_10") (pintype "bidirectional"))
    )
    (net (code "102") (name "Net-(IC2A-7Q)") (class "Default")
      (node (ref "IC2") (pin "13") (pinfunction "7Q_13") (pintype "tri_state"))
      (node (ref "IC3") (pin "11") (pinfunction "A1_11") (pintype "bidirectional"))
    )
    (net (code "103") (name "Net-(IC2A-8Q)") (class "Default")
      (node (ref "IC2") (pin "12") (pinfunction "8Q_12") (pintype "tri_state"))
      (node (ref "IC3") (pin "12") (pinfunction "A0_12") (pintype "bidirectional"))
    )
    (net (code "104") (name "Net-(IC4-3V3OUT)") (class "Default")
      (node (ref "C4") (pin "1") (pinfunction "1_1") (pintype "passive"))
      (node (ref "IC4") (pin "17") (pinfunction "3V3OUT_17") (pintype "output"))
    )
    (net (code "105") (name "Net-(IC4-CBUS0)") (class "Default")
      (node (ref "IC4") (pin "23") (pinfunction "CBUS0_23") (pintype "bidirectional"))
      (node (ref "R12") (pin "1") (pinfunction "1_1") (pintype "passive"))
    )
    (net (code "106") (name "Net-(IC4-CBUS1)") (class "Default")
      (node (ref "IC4") (pin "22") (pinfunction "CBUS1_22") (pintype "bidirectional"))
      (node (ref "R13") (pin "1") (pinfunction "1_1") (pintype "passive"))
    )
    (net (code "107") (name "Net-(IC4-USBDM)") (class "Default")
      (node (ref "IC4") (pin "16") (pinfunction "USBDM_16") (pintype "bidirectional"))
      (node (ref "USB") (pin "2") (pinfunction "2_2") (pintype "input"))
    )
    (net (code "108") (name "Net-(IC4-USBDP)") (class "Default")
      (node (ref "IC4") (pin "15") (pinfunction "USBDP_15") (pintype "bidirectional"))
      (node (ref "USB") (pin "3") (pinfunction "3_3") (pintype "input"))
    )
    (net (code "109") (name "Net-(IC4-~{RESET})") (class "Default")
      (node (ref "IC4") (pin "19") (pinfunction "~{RESET}_19") (pintype "input"))
      (node (ref "R10") (pin "2") (pinfunction "2_2") (pintype "passive"))
      (node (ref "R11") (pin "2") (pinfunction "2_2") (pintype "passive"))
    )
    (net (code "110") (name "Net-(IC5A-O)") (class "Default")
      (node (ref "IC5") (pin "3") (pinfunction "O_3") (pintype "tri_state"))
      (node (ref "SD") (pin "5") (pinfunction "5_5") (pintype "input"))
    )
    (net (code "111") (name "Net-(IC5B-O)") (class "Default")
      (node (ref "IC5") (pin "6") (pinfunction "O_6") (pintype "tri_state"))
      (node (ref "SD") (pin "2") (pinfunction "2_2") (pintype "input"))
    )
    (net (code "112") (name "Net-(IC5C-O)") (class "Default")
      (node (ref "IC5") (pin "8") (pinfunction "O_8") (pintype "tri_state"))
      (node (ref "SD") (pin "1") (pinfunction "1_1") (pintype "input"))
    )
    (net (code "113") (name "Net-(IC6-ADJ)") (class "Default")
      (node (ref "IC6") (pin "1") (pinfunction "ADJ_1") (pintype "input"))
      (node (ref "R1") (pin "1") (pinfunction "1_1") (pintype "passive"))
      (node (ref "R2") (pin "A") (pinfunction "A_A") (pintype "passive"))
      (node (ref "R2") (pin "S") (pinfunction "S_S") (pintype "passive"))
    )
    (net (code "114") (name "Net-(ISP-+5V)") (class "Default")
      (node (ref "ISP") (pin "2") (pinfunction "+5V_2") (pintype "power_in"))
      (node (ref "JP2") (pin "1") (pinfunction "1_1") (pintype "passive"))
    )
    (net (code "115") (name "Net-(JP3-Pad2)") (class "Default")
      (node (ref "JP3") (pin "2") (pinfunction "2_2") (pintype "passive"))
      (node (ref "SPI") (pin "10") (pinfunction "10_10") (pintype "passive"))
    )
    (net (code "116") (name "Net-(LED1-PadC)") (class "Default")
      (node (ref "LED1") (pin "C") (pinfunction "C_C") (pintype "passive"))
      (node (ref "R13") (pin "2") (pinfunction "2_2") (pintype "passive"))
    )
    (net (code "117") (name "Net-(LED2-PadC)") (class "Default")
      (node (ref "LED2") (pin "C") (pinfunction "C_C") (pintype "passive"))
      (node (ref "R12") (pin "2") (pinfunction "2_2") (pintype "passive"))
    )
    (net (code "118") (name "Net-(LED3-PadA)") (class "Default")
      (node (ref "LED3") (pin "A") (pinfunction "A_A") (pintype "passive"))
      (node (ref "R16") (pin "1") (pinfunction "1_1") (pintype "passive"))
    )
    (net (code "119") (name "Net-(LED4-PadA)") (class "Default")
      (node (ref "LED4") (pin "A") (pinfunction "A_A") (pintype "passive"))
      (node (ref "R15") (pin "1") (pinfunction "1_1") (pintype "passive"))
    )
    (net (code "120") (name "Net-(LED5-PadA)") (class "Default")
      (node (ref "LED5") (pin "A") (pinfunction "A_A") (pintype "passive"))
      (node (ref "R8") (pin "1") (pinfunction "1_1") (pintype "passive"))
    )
    (net (code "121") (name "Net-(LED6-PadA)") (class "Default")
      (node (ref "LED6") (pin "A") (pinfunction "A_A") (pintype "passive"))
      (node (ref "R7") (pin "1") (pinfunction "1_1") (pintype "passive"))
    )
    (net (code "122") (name "Net-(LM2576-5-FB)") (class "Default")
      (node (ref "C12") (pin "+") (pinfunction "+_+") (pintype "passive"))
      (node (ref "C13") (pin "1") (pinfunction "1_1") (pintype "passive"))
      (node (ref "H1") (pin "P$2") (pinfunction "P$2_P$2") (pintype "bidirectional"))
      (node (ref "JP4") (pin "1") (pinfunction "1_1") (pintype "passive"))
      (node (ref "LM2576-5") (pin "P$4") (pinfunction "FB_P$4") (pintype "input"))
    )
    (net (code "123") (name "Net-(LM2576-5-OUT)") (class "Default")
      (node (ref "D2") (pin "C") (pinfunction "C_C") (pintype "passive"))
      (node (ref "H1") (pin "P$1") (pinfunction "P$1_P$1") (pintype "bidirectional"))
      (node (ref "LM2576-5") (pin "P$2") (pinfunction "OUT_P$2") (pintype "power_in"))
    )
    (net (code "124") (name "VCC") (class "Default")
      (node (ref "AD-A") (pin "10") (pinfunction "VCC_10") (pintype "power_in"))
      (node (ref "AD-B") (pin "10") (pinfunction "VCC_10") (pintype "power_in"))
      (node (ref "C14") (pin "2") (pinfunction "2_2") (pintype "passive"))
      (node (ref "C15") (pin "2") (pinfunction "2_2") (pintype "passive"))
      (node (ref "C16") (pin "2") (pinfunction "2_2") (pintype "passive"))
      (node (ref "C17") (pin "2") (pinfunction "2_2") (pintype "passive"))
      (node (ref "C18") (pin "2") (pinfunction "2_2") (pintype "passive"))
      (node (ref "C19") (pin "2") (pinfunction "2_2") (pintype "passive"))
      (node (ref "C20") (pin "2") (pinfunction "2_2") (pintype "passive"))
      (node (ref "C21") (pin "2") (pinfunction "2_2") (pintype "passive"))
      (node (ref "C22") (pin "2") (pinfunction "2_2") (pintype "passive"))
      (node (ref "C23") (pin "2") (pinfunction "2_2") (pintype "passive"))
      (node (ref "C28") (pin "+") (pinfunction "+_+") (pintype "passive"))
      (node (ref "C5") (pin "2") (pinfunction "2_2") (pintype "passive"))
      (node (ref "C6") (pin "2") (pinfunction "2_2") (pintype "passive"))
      (node (ref "C7") (pin "2") (pinfunction "2_2") (pintype "passive"))
      (node (ref "C8") (pin "2") (pinfunction "2_2") (pintype "passive"))
      (node (ref "C9") (pin "2") (pinfunction "2_2") (pintype "passive"))
      (node (ref "IC1") (pin "10") (pinfunction "VCC_10") (pintype "power_in"))
      (node (ref "IC1") (pin "100") (pinfunction "AVCC_100") (pintype "power_in"))
      (node (ref "IC1") (pin "31") (pinfunction "VCC1_31") (pintype "power_in"))
      (node (ref "IC1") (pin "61") (pinfunction "VCC2_61") (pintype "power_in"))
      (node (ref "IC1") (pin "80") (pinfunction "VCC3_80") (pintype "power_in"))
      (node (ref "IC3") (pin "32") (pinfunction "VCC_32") (pintype "power_in"))
      (node (ref "IC4") (pin "20") (pinfunction "VCC_20") (pintype "power_in"))
      (node (ref "IC4") (pin "4") (pinfunction "VCCIO_4") (pintype "power_in"))
      (node (ref "IC6") (pin "3") (pinfunction "IN_3") (pintype "input"))
      (node (ref "JP1") (pin "2") (pinfunction "2_2") (pintype "passive"))
      (node (ref "JP2") (pin "2") (pinfunction "2_2") (pintype "passive"))
      (node (ref "JP3") (pin "1") (pinfunction "1_1") (pintype "passive"))
      (node (ref "JP4") (pin "2") (pinfunction "2_2") (pintype "passive"))
      (node (ref "JP5") (pin "2") (pinfunction "2_2") (pintype "passive"))
      (node (ref "LED1") (pin "A") (pinfunction "A_A") (pintype "passive"))
      (node (ref "LED2") (pin "A") (pinfunction "A_A") (pintype "passive"))
      (node (ref "P1") (pin "10") (pinfunction "VCC_10") (pintype "power_in"))
      (node (ref "P2") (pin "10") (pinfunction "VCC_10") (pintype "power_in"))
      (node (ref "P3") (pin "10") (pinfunction "VCC_10") (pintype "power_in"))
      (node (ref "R14") (pin "1") (pinfunction "1_1") (pintype "passive"))
      (node (ref "RS1") (pin "4") (pinfunction "VCC_4") (pintype "bidirectional"))
      (node (ref "RS2") (pin "4") (pinfunction "VCC_4") (pintype "bidirectional"))
      (node (ref "RS3") (pin "4") (pinfunction "VCC_4") (pintype "bidirectional"))
    )
    (net (code "125") (name "VDD") (class "Default")
      (node (ref "C24") (pin "2") (pinfunction "2_2") (pintype "passive"))
      (node (ref "C26") (pin "2") (pinfunction "2_2") (pintype "passive"))
      (node (ref "C27") (pin "+") (pinfunction "+_+") (pintype "passive"))
      (node (ref "IC5") (pin "14") (pinfunction "VCC_14") (pintype "power_in"))
      (node (ref "IC6") (pin "2") (pinfunction "OUT_2") (pintype "passive"))
      (node (ref "R1") (pin "2") (pinfunction "2_2") (pintype "passive"))
      (node (ref "SD") (pin "4") (pinfunction "4_4") (pintype "input"))
    )
    (net (code "126") (name "unconnected-(IC4-CBUS2-Pad13)") (class "Default")
      (node (ref "IC4") (pin "13") (pinfunction "CBUS2_13") (pintype "bidirectional"))
    )
    (net (code "127") (name "unconnected-(IC4-CBUS3-Pad14)") (class "Default")
      (node (ref "IC4") (pin "14") (pinfunction "CBUS3_14") (pintype "bidirectional"))
    )
    (net (code "128") (name "unconnected-(IC4-CBUS4-Pad12)") (class "Default")
      (node (ref "IC4") (pin "12") (pinfunction "CBUS4_12") (pintype "bidirectional"))
    )
    (net (code "129") (name "unconnected-(IC4-OSCI-Pad27)") (class "Default")
      (node (ref "IC4") (pin "27") (pinfunction "OSCI_27") (pintype "input"))
    )
    (net (code "130") (name "unconnected-(IC4-OSCO-Pad28)") (class "Default")
      (node (ref "IC4") (pin "28") (pinfunction "OSCO_28") (pintype "output"))
    )
    (net (code "131") (name "unconnected-(IC4-~{CTS}-Pad11)") (class "Default")
      (node (ref "IC4") (pin "11") (pinfunction "~{CTS}_11") (pintype "input"))
    )
    (net (code "132") (name "unconnected-(IC4-~{DCD}-Pad10)") (class "Default")
      (node (ref "IC4") (pin "10") (pinfunction "~{DCD}_10") (pintype "input"))
    )
    (net (code "133") (name "unconnected-(IC4-~{DSR}-Pad9)") (class "Default")
      (node (ref "IC4") (pin "9") (pinfunction "~{DSR}_9") (pintype "input"))
    )
    (net (code "134") (name "unconnected-(IC4-~{DTR}-Pad2)") (class "Default")
      (node (ref "IC4") (pin "2") (pinfunction "~{DTR}_2") (pintype "output"))
    )
    (net (code "135") (name "unconnected-(IC4-~{RI}-Pad6)") (class "Default")
      (node (ref "IC4") (pin "6") (pinfunction "~{RI}_6") (pintype "input"))
    )
    (net (code "136") (name "unconnected-(IC4-~{RTS}-Pad3)") (class "Default")
      (node (ref "IC4") (pin "3") (pinfunction "~{RTS}_3") (pintype "output"))
    )
    (net (code "137") (name "unconnected-(ISP-LED-Pad3)") (class "Default")
      (node (ref "ISP") (pin "3") (pinfunction "LED_3") (pintype "output"))
    )
    (net (code "138") (name "unconnected-(SD-Pad8)") (class "Default")
      (node (ref "SD") (pin "8") (pinfunction "8_8") (pintype "input"))
    )
    (net (code "139") (name "unconnected-(SD-Pad9)") (class "Default")
      (node (ref "SD") (pin "9") (pinfunction "9_9") (pintype "input"))
    )
    (net (code "140") (name "unconnected-(USB-Pad4)") (class "Default")
      (node (ref "USB") (pin "4") (pinfunction "4_4") (pintype "input"))
    )
    (net (code "141") (name "unconnected-(X1-Pad3)") (class "Default")
      (node (ref "X1") (pin "3") (pinfunction "3_3") (pintype "passive"))
    )
  )
)
